# Underwater_ROV_CurrentSense.net
KiCad netlist of a schematic drawn in Altium Designer
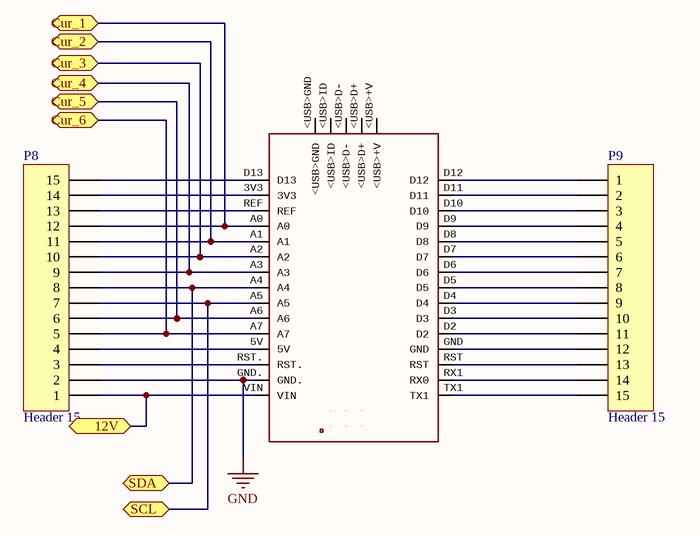
[diagram p0: Underwater_ROV_CurrentSense.SchDoc]

(export (version "E")
  (design (tool "Eeschema 10.0.6"))
  (components
    (comp (ref "Nano_Cur1")
      (value "Device for representing an Arduino Nano board with a footprint in an EAGLE design. Created by Dave Young for Element14. More EAGLE documentation at: http://www.element14.com/community/community/knode/cadsoft_eagle")
      (footprint "ARDUINO_NANO")
      (libsource (lib "E14_Arduino_revC") (part "ARDUINO_NANO"))
    )
    (comp (ref "P8")
      (value "Header 15")
      (footprint "HDR1X15")
      (description "Header, 15-Pin")
      (fields (field (name "PUBLISHER") "Altium Limited"))
      (libsource (lib "") (part "Header 15_1"))
    )
    (comp (ref "P9")
      (value "Header 15")
      (footprint "HDR1X15")
      (description "Header, 15-Pin")
      (fields (field (name "PUBLISHER") "Altium Limited"))
      (libsource (lib "Miscellaneous Connectors") (part "Header 15"))
    )
  )
  (nets
    (net (code "1") (name "/12V") (class "Default")
      (node (ref "Nano_Cur1") (pin "VIN") (pinfunction "VIN_VIN") (pintype "passive"))
      (node (ref "P8") (pin "1") (pinfunction "1_1") (pintype "passive"))
    )
    (net (code "2") (name "/Cur_1") (class "Default")
      (node (ref "Nano_Cur1") (pin "A0") (pinfunction "A0_A0") (pintype "passive"))
      (node (ref "P8") (pin "12") (pinfunction "12_12") (pintype "passive"))
    )
    (net (code "3") (name "/Cur_2") (class "Default")
      (node (ref "Nano_Cur1") (pin "A1") (pinfunction "A1_A1") (pintype "passive"))
      (node (ref "P8") (pin "11") (pinfunction "11_11") (pintype "passive"))
    )
    (net (code "4") (name "/Cur_3") (class "Default")
      (node (ref "Nano_Cur1") (pin "A2") (pinfunction "A2_A2") (pintype "passive"))
      (node (ref "P8") (pin "10") (pinfunction "10_10") (pintype "passive"))
    )
    (net (code "5") (name "/Cur_4") (class "Default")
      (node (ref "Nano_Cur1") (pin "A3") (pinfunction "A3_A3") (pintype "passive"))
      (node (ref "P8") (pin "9") (pinfunction "9_9") (pintype "passive"))
    )
    (net (code "6") (name "/Cur_5") (class "Default")
      (node (ref "Nano_Cur1") (pin "A6") (pinfunction "A6_A6") (pintype "passive"))
      (node (ref "P8") (pin "6") (pinfunction "6_6") (pintype "passive"))
    )
    (net (code "7") (name "/Cur_6") (class "Default")
      (node (ref "Nano_Cur1") (pin "A7") (pinfunction "A7_A7") (pintype "passive"))
      (node (ref "P8") (pin "5") (pinfunction "5_5") (pintype "passive"))
    )
    (net (code "8") (name "/SCL") (class "Default")
      (node (ref "Nano_Cur1") (pin "A5") (pinfunction "A5_A5") (pintype "passive"))
      (node (ref "P8") (pin "7") (pinfunction "7_7") (pintype "passive"))
    )
    (net (code "9") (name "/SDA") (class "Default")
      (node (ref "Nano_Cur1") (pin "A4") (pinfunction "A4_A4") (pintype "passive"))
      (node (ref "P8") (pin "8") (pinfunction "8_8") (pintype "passive"))
    )
    (net (code "10") (name "GND") (class "Default")
      (node (ref "Nano_Cur1") (pin "GND.") (pinfunction "GND._GND.") (pintype "passive"))
      (node (ref "P8") (pin "2") (pinfunction "2_2") (pintype "passive"))
    )
    (net (code "11") (name "Net-(Nano_Cur1-Pad3V3)") (class "Default")
      (node (ref "Nano_Cur1") (pin "3V3") (pinfunction "3V3_3V3") (pintype "passive"))
      (node (ref "P8") (pin "14") (pinfunction "14_14") (pintype "passive"))
    )
    (net (code "12") (name "Net-(Nano_Cur1-Pad5V)") (class "Default")
      (node (ref "Nano_Cur1") (pin "5V") (pinfunction "5V_5V") (pintype "passive"))
      (node (ref "P8") (pin "4") (pinfunction "4_4") (pintype "passive"))
    )
    (net (code "13") (name "Net-(Nano_Cur1-PadD2)") (class "Default")
      (node (ref "Nano_Cur1") (pin "D2") (pinfunction "D2_D2") (pintype "passive"))
      (node (ref "P9") (pin "11") (pinfunction "11_11") (pintype "passive"))
    )
    (net (code "14") (name "Net-(Nano_Cur1-PadD3)") (class "Default")
      (node (ref "Nano_Cur1") (pin "D3") (pinfunction "D3_D3") (pintype "passive"))
      (node (ref "P9") (pin "10") (pinfunction "10_10") (pintype "passive"))
    )
    (net (code "15") (name "Net-(Nano_Cur1-PadD4)") (class "Default")
      (node (ref "Nano_Cur1") (pin "D4") (pinfunction "D4_D4") (pintype "passive"))
      (node (ref "P9") (pin "9") (pinfunction "9_9") (pintype "passive"))
    )
    (net (code "16") (name "Net-(Nano_Cur1-PadD5)") (class "Default")
      (node (ref "Nano_Cur1") (pin "D5") (pinfunction "D5_D5") (pintype "passive"))
      (node (ref "P9") (pin "8") (pinfunction "8_8") (pintype "passive"))
    )
    (net (code "17") (name "Net-(Nano_Cur1-PadD6)") (class "Default")
      (node (ref "Nano_Cur1") (pin "D6") (pinfunction "D6_D6") (pintype "passive"))
      (node (ref "P9") (pin "7") (pinfunction "7_7") (pintype "passive"))
    )
    (net (code "18") (name "Net-(Nano_Cur1-PadD7)") (class "Default")
      (node (ref "Nano_Cur1") (pin "D7") (pinfunction "D7_D7") (pintype "passive"))
      (node (ref "P9") (pin "6") (pinfunction "6_6") (pintype "passive"))
    )
    (net (code "19") (name "Net-(Nano_Cur1-PadD8)") (class "Default")
      (node (ref "Nano_Cur1") (pin "D8") (pinfunction "D8_D8") (pintype "passive"))
      (node (ref "P9") (pin "5") (pinfunction "5_5") (pintype "passive"))
    )
    (net (code "20") (name "Net-(Nano_Cur1-PadD9)") (class "Default")
      (node (ref "Nano_Cur1") (pin "D9") (pinfunction "D9_D9") (pintype "passive"))
      (node (ref "P9") (pin "4") (pinfunction "4_4") (pintype "passive"))
    )
    (net (code "21") (name "Net-(Nano_Cur1-PadD10)") (class "Default")
      (node (ref "Nano_Cur1") (pin "D10") (pinfunction "D10_D10") (pintype "passive"))
      (node (ref "P9") (pin "3") (pinfunction "3_3") (pintype "passive"))
    )
    (net (code "22") (name "Net-(Nano_Cur1-PadD11)") (class "Default")
      (node (ref "Nano_Cur1") (pin "D11") (pinfunction "D11_D11") (pintype "passive"))
      (node (ref "P9") (pin "2") (pinfunction "2_2") (pintype "passive"))
    )
    (net (code "23") (name "Net-(Nano_Cur1-PadD12)") (class "Default")
      (node (ref "Nano_Cur1") (pin "D12") (pinfunction "D12_D12") (pintype "passive"))
      (node (ref "P9") (pin "1") (pinfunction "1_1") (pintype "passive"))
    )
    (net (code "24") (name "Net-(Nano_Cur1-PadD13)") (class "Default")
      (node (ref "Nano_Cur1") (pin "D13") (pinfunction "D13_D13") (pintype "passive"))
      (node (ref "P8") (pin "15") (pinfunction "15_15") (pintype "passive"))
    )
    (net (code "25") (name "Net-(Nano_Cur1-PadGND)") (class "Default")
      (node (ref "Nano_Cur1") (pin "GND") (pinfunction "GND_GND") (pintype "passive"))
      (node (ref "P9") (pin "12") (pinfunction "12_12") (pintype "passive"))
    )
    (net (code "26") (name "Net-(Nano_Cur1-PadREF)") (class "Default")
      (node (ref "Nano_Cur1") (pin "REF") (pinfunction "REF_REF") (pintype "passive"))
      (node (ref "P8") (pin "13") (pinfunction "13_13") (pintype "passive"))
    )
    (net (code "27") (name "Net-(Nano_Cur1-PadRST)") (class "Default")
      (node (ref "Nano_Cur1") (pin "RST") (pinfunction "RST_RST") (pintype "passive"))
      (node (ref "P9") (pin "13") (pinfunction "13_13") (pintype "passive"))
    )
    (net (code "28") (name "Net-(Nano_Cur1-PadRST.)") (class "Default")
      (node (ref "Nano_Cur1") (pin "RST.") (pinfunction "RST._RST.") (pintype "passive"))
      (node (ref "P8") (pin "3") (pinfunction "3_3") (pintype "passive"))
    )
    (net (code "29") (name "Net-(Nano_Cur1-PadTX1)") (class "Default")
      (node (ref "Nano_Cur1") (pin "TX1") (pinfunction "TX1_TX1") (pintype "passive"))
      (node (ref "P9") (pin "15") (pinfunction "15_15") (pintype "passive"))
    )
    (net (code "30") (name "Net-(Nano_Cur1-RX0)") (class "Default")
      (node (ref "Nano_Cur1") (pin "RX1") (pinfunction "RX0_RX1") (pintype "passive"))
      (node (ref "P9") (pin "14") (pinfunction "14_14") (pintype "passive"))
    )
    (net (code "31") (name "unconnected-(Nano_Cur1-Pad5V.)") (class "Default")
      (node (ref "Nano_Cur1") (pin "5V.") (pinfunction "5V._5V.") (pintype "passive"))
    )
    (net (code "32") (name "unconnected-(Nano_Cur1-Pad<USB>+V)") (class "Default")
      (node (ref "Nano_Cur1") (pin "<USB>+V") (pinfunction "<USB>+V_<USB>+V") (pintype "passive"))
    )
    (net (code "33") (name "unconnected-(Nano_Cur1-Pad<USB>D+)") (class "Default")
      (node (ref "Nano_Cur1") (pin "<USB>D+") (pinfunction "<USB>D+_<USB>D+") (pintype "passive"))
    )
    (net (code "34") (name "unconnected-(Nano_Cur1-Pad<USB>D-)") (class "Default")
      (node (ref "Nano_Cur1") (pin "<USB>D-") (pinfunction "<USB>D-_<USB>D-") (pintype "passive"))
    )
    (net (code "35") (name "unconnected-(Nano_Cur1-Pad<USB>GND)") (class "Default")
      (node (ref "Nano_Cur1") (pin "<USB>GND") (pinfunction "<USB>GND_<USB>GND") (pintype "passive"))
    )
    (net (code "36") (name "unconnected-(Nano_Cur1-Pad<USB>ID)") (class "Default")
      (node (ref "Nano_Cur1") (pin "<USB>ID") (pinfunction "<USB>ID_<USB>ID") (pintype "passive"))
    )
    (net (code "37") (name "unconnected-(Nano_Cur1-PadGND_)") (class "Default")
      (node (ref "Nano_Cur1") (pin "GND_") (pinfunction "GND__GND_") (pintype "passive"))
    )
    (net (code "38") (name "unconnected-(Nano_Cur1-PadMISO)") (class "Default")
      (node (ref "Nano_Cur1") (pin "MISO") (pinfunction "MISO_MISO") (pintype "passive"))
    )
    (net (code "39") (name "unconnected-(Nano_Cur1-PadMOSI)") (class "Default")
      (node (ref "Nano_Cur1") (pin "MOSI") (pinfunction "MOSI_MOSI") (pintype "passive"))
    )
    (net (code "40") (name "unconnected-(Nano_Cur1-PadRESET..)") (class "Default")
      (node (ref "Nano_Cur1") (pin "RESET..") (pinfunction "RESET.._RESET..") (pintype "passive"))
    )
    (net (code "41") (name "unconnected-(Nano_Cur1-PadSCK)") (class "Default")
      (node (ref "Nano_Cur1") (pin "SCK") (pinfunction "SCK_SCK") (pintype "passive"))
    )
  )
)
